# MEZ_Sheet1.net
KiCad netlist of a schematic drawn in Altium Designer
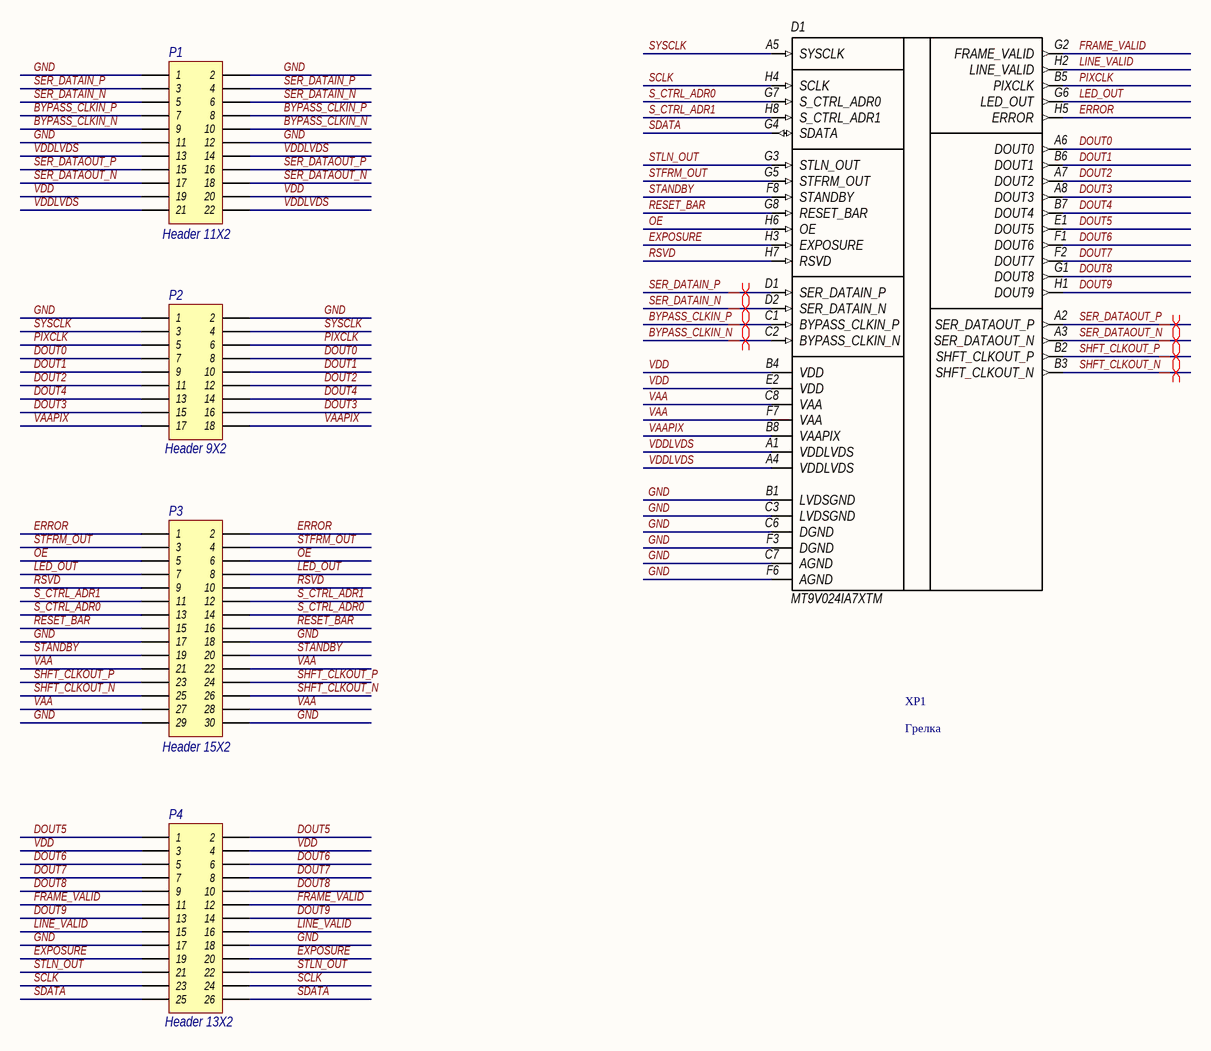
[diagram p0: MEZ_Sheet1.SchDoc]

(export (version "E")
  (design (tool "Eeschema 10.0.6"))
  (components
    (comp (ref "D1")
      (value "MT9V024IA7XTM")
      (footprint "MT9V024IA7XTM")
      (description "КМОП матрица WVGA")
      (libsource (lib "VPL") (part "MT9V024IA7XTM"))
    )
    (comp (ref "P1")
      (value "Header 11X2")
      (footprint "HDR2X11")
      (description "Header, 11-Pin, Dual row")
      (fields (field (name "PUBLISHER") "Altium Limited"))
      (libsource (lib "Miscellaneous Connectors") (part "Header 11X2"))
    )
    (comp (ref "P2")
      (value "Header 9X2")
      (footprint "HDR2X9")
      (description "Header, 9-Pin, Dual row")
      (fields (field (name "PUBLISHER") "Altium Limited"))
      (libsource (lib "Miscellaneous Connectors") (part "Header 9X2"))
    )
    (comp (ref "P3")
      (value "Header 15X2")
      (footprint "HDR2X15")
      (description "Header, 15-Pin, Dual row")
      (fields (field (name "PUBLISHER") "Altium Limited"))
      (libsource (lib "Miscellaneous Connectors") (part "Header 15X2"))
    )
    (comp (ref "P4")
      (value "Header 13X2")
      (footprint "HDR2X13")
      (description "Header, 13-Pin, Dual row")
      (fields (field (name "PUBLISHER") "Altium Limited"))
      (libsource (lib "Miscellaneous Connectors") (part "Header 13X2"))
    )
    (comp (ref "XP1") (value "Грелка") (footprint "Грелка") (libsource (lib "VPL") (part "Грелка")))
  )
  (nets
    (net (code "1") (name "/BYPASS_CLKIN_N") (class "Default")
      (node (ref "D1") (pin "C2") (pinfunction "BYPASS_CLKIN_N_C2") (pintype "input"))
      (node (ref "P1") (pin "10") (pinfunction "10_10") (pintype "passive"))
      (node (ref "P1") (pin "9") (pinfunction "9_9") (pintype "passive"))
    )
    (net (code "2") (name "/BYPASS_CLKIN_P") (class "Default")
      (node (ref "D1") (pin "C1") (pinfunction "BYPASS_CLKIN_P_C1") (pintype "input"))
      (node (ref "P1") (pin "7") (pinfunction "7_7") (pintype "passive"))
      (node (ref "P1") (pin "8") (pinfunction "8_8") (pintype "passive"))
    )
    (net (code "3") (name "/DOUT0") (class "Default")
      (node (ref "D1") (pin "A6") (pinfunction "DOUT0_A6") (pintype "output"))
      (node (ref "P2") (pin "7") (pinfunction "7_7") (pintype "passive"))
      (node (ref "P2") (pin "8") (pinfunction "8_8") (pintype "passive"))
    )
    (net (code "4") (name "/DOUT1") (class "Default")
      (node (ref "D1") (pin "B6") (pinfunction "DOUT1_B6") (pintype "output"))
      (node (ref "P2") (pin "10") (pinfunction "10_10") (pintype "passive"))
      (node (ref "P2") (pin "9") (pinfunction "9_9") (pintype "passive"))
    )
    (net (code "5") (name "/DOUT2") (class "Default")
      (node (ref "D1") (pin "A7") (pinfunction "DOUT2_A7") (pintype "output"))
      (node (ref "P2") (pin "11") (pinfunction "11_11") (pintype "passive"))
      (node (ref "P2") (pin "12") (pinfunction "12_12") (pintype "passive"))
    )
    (net (code "6") (name "/DOUT3") (class "Default")
      (node (ref "D1") (pin "A8") (pinfunction "DOUT3_A8") (pintype "output"))
      (node (ref "P2") (pin "15") (pinfunction "15_15") (pintype "passive"))
      (node (ref "P2") (pin "16") (pinfunction "16_16") (pintype "passive"))
    )
    (net (code "7") (name "/DOUT4") (class "Default")
      (node (ref "D1") (pin "B7") (pinfunction "DOUT4_B7") (pintype "output"))
      (node (ref "P2") (pin "13") (pinfunction "13_13") (pintype "passive"))
      (node (ref "P2") (pin "14") (pinfunction "14_14") (pintype "passive"))
    )
    (net (code "8") (name "/DOUT5") (class "Default")
      (node (ref "D1") (pin "E1") (pinfunction "DOUT5_E1") (pintype "output"))
      (node (ref "P4") (pin "1") (pinfunction "1_1") (pintype "passive"))
      (node (ref "P4") (pin "2") (pinfunction "2_2") (pintype "passive"))
    )
    (net (code "9") (name "/DOUT6") (class "Default")
      (node (ref "D1") (pin "F1") (pinfunction "DOUT6_F1") (pintype "output"))
      (node (ref "P4") (pin "5") (pinfunction "5_5") (pintype "passive"))
      (node (ref "P4") (pin "6") (pinfunction "6_6") (pintype "passive"))
    )
    (net (code "10") (name "/DOUT7") (class "Default")
      (node (ref "D1") (pin "F2") (pinfunction "DOUT7_F2") (pintype "output"))
      (node (ref "P4") (pin "7") (pinfunction "7_7") (pintype "passive"))
      (node (ref "P4") (pin "8") (pinfunction "8_8") (pintype "passive"))
    )
    (net (code "11") (name "/DOUT8") (class "Default")
      (node (ref "D1") (pin "G1") (pinfunction "DOUT8_G1") (pintype "output"))
      (node (ref "P4") (pin "10") (pinfunction "10_10") (pintype "passive"))
      (node (ref "P4") (pin "9") (pinfunction "9_9") (pintype "passive"))
    )
    (net (code "12") (name "/DOUT9") (class "Default")
      (node (ref "D1") (pin "H1") (pinfunction "DOUT9_H1") (pintype "output"))
      (node (ref "P4") (pin "13") (pinfunction "13_13") (pintype "passive"))
      (node (ref "P4") (pin "14") (pinfunction "14_14") (pintype "passive"))
    )
    (net (code "13") (name "/ERROR") (class "Default")
      (node (ref "D1") (pin "H5") (pinfunction "ERROR_H5") (pintype "output"))
      (node (ref "P3") (pin "1") (pinfunction "1_1") (pintype "passive"))
      (node (ref "P3") (pin "2") (pinfunction "2_2") (pintype "passive"))
    )
    (net (code "14") (name "/EXPOSURE") (class "Default")
      (node (ref "D1") (pin "H3") (pinfunction "EXPOSURE_H3") (pintype "input"))
      (node (ref "P4") (pin "19") (pinfunction "19_19") (pintype "passive"))
      (node (ref "P4") (pin "20") (pinfunction "20_20") (pintype "passive"))
    )
    (net (code "15") (name "/FRAME_VALID") (class "Default")
      (node (ref "D1") (pin "G2") (pinfunction "FRAME_VALID_G2") (pintype "output"))
      (node (ref "P4") (pin "11") (pinfunction "11_11") (pintype "passive"))
      (node (ref "P4") (pin "12") (pinfunction "12_12") (pintype "passive"))
    )
    (net (code "16") (name "/GND") (class "Default")
      (node (ref "D1") (pin "B1") (pinfunction "LVDSGND_B1") (pintype "passive"))
      (node (ref "D1") (pin "C3") (pinfunction "LVDSGND_C3") (pintype "passive"))
      (node (ref "D1") (pin "C6") (pinfunction "DGND_C6") (pintype "passive"))
      (node (ref "D1") (pin "C7") (pinfunction "AGND_C7") (pintype "passive"))
      (node (ref "D1") (pin "F3") (pinfunction "DGND_F3") (pintype "passive"))
      (node (ref "D1") (pin "F6") (pinfunction "AGND_F6") (pintype "passive"))
      (node (ref "P1") (pin "1") (pinfunction "1_1") (pintype "passive"))
      (node (ref "P1") (pin "11") (pinfunction "11_11") (pintype "passive"))
      (node (ref "P1") (pin "12") (pinfunction "12_12") (pintype "passive"))
      (node (ref "P1") (pin "2") (pinfunction "2_2") (pintype "passive"))
      (node (ref "P2") (pin "1") (pinfunction "1_1") (pintype "passive"))
      (node (ref "P2") (pin "2") (pinfunction "2_2") (pintype "passive"))
      (node (ref "P3") (pin "17") (pinfunction "17_17") (pintype "passive"))
      (node (ref "P3") (pin "18") (pinfunction "18_18") (pintype "passive"))
      (node (ref "P3") (pin "29") (pinfunction "29_29") (pintype "passive"))
      (node (ref "P3") (pin "30") (pinfunction "30_30") (pintype "passive"))
      (node (ref "P4") (pin "17") (pinfunction "17_17") (pintype "passive"))
      (node (ref "P4") (pin "18") (pinfunction "18_18") (pintype "passive"))
    )
    (net (code "17") (name "/LED_OUT") (class "Default")
      (node (ref "D1") (pin "G6") (pinfunction "LED_OUT_G6") (pintype "output"))
      (node (ref "P3") (pin "7") (pinfunction "7_7") (pintype "passive"))
      (node (ref "P3") (pin "8") (pinfunction "8_8") (pintype "passive"))
    )
    (net (code "18") (name "/LINE_VALID") (class "Default")
      (node (ref "D1") (pin "H2") (pinfunction "LINE_VALID_H2") (pintype "output"))
      (node (ref "P4") (pin "15") (pinfunction "15_15") (pintype "passive"))
      (node (ref "P4") (pin "16") (pinfunction "16_16") (pintype "passive"))
    )
    (net (code "19") (name "/OE") (class "Default")
      (node (ref "D1") (pin "H6") (pinfunction "OE_H6") (pintype "input"))
      (node (ref "P3") (pin "5") (pinfunction "5_5") (pintype "passive"))
      (node (ref "P3") (pin "6") (pinfunction "6_6") (pintype "passive"))
    )
    (net (code "20") (name "/PIXCLK") (class "Default")
      (node (ref "D1") (pin "B5") (pinfunction "PIXCLK_B5") (pintype "output"))
      (node (ref "P2") (pin "5") (pinfunction "5_5") (pintype "passive"))
      (node (ref "P2") (pin "6") (pinfunction "6_6") (pintype "passive"))
    )
    (net (code "21") (name "/RESET_BAR") (class "Default")
      (node (ref "D1") (pin "G8") (pinfunction "RESET_BAR_G8") (pintype "input"))
      (node (ref "P3") (pin "15") (pinfunction "15_15") (pintype "passive"))
      (node (ref "P3") (pin "16") (pinfunction "16_16") (pintype "passive"))
    )
    (net (code "22") (name "/RSVD") (class "Default")
      (node (ref "D1") (pin "H7") (pinfunction "RSVD_H7") (pintype "input"))
      (node (ref "P3") (pin "10") (pinfunction "10_10") (pintype "passive"))
      (node (ref "P3") (pin "9") (pinfunction "9_9") (pintype "passive"))
    )
    (net (code "23") (name "/SCLK") (class "Default")
      (node (ref "D1") (pin "H4") (pinfunction "SCLK_H4") (pintype "input"))
      (node (ref "P4") (pin "23") (pinfunction "23_23") (pintype "passive"))
      (node (ref "P4") (pin "24") (pinfunction "24_24") (pintype "passive"))
    )
    (net (code "24") (name "/SDATA") (class "Default")
      (node (ref "D1") (pin "G4") (pinfunction "SDATA_G4") (pintype "bidirectional"))
      (node (ref "P4") (pin "25") (pinfunction "25_25") (pintype "passive"))
      (node (ref "P4") (pin "26") (pinfunction "26_26") (pintype "passive"))
    )
    (net (code "25") (name "/SER_DATAIN_N") (class "Default")
      (node (ref "D1") (pin "D2") (pinfunction "SER_DATAIN_N_D2") (pintype "input"))
      (node (ref "P1") (pin "5") (pinfunction "5_5") (pintype "passive"))
      (node (ref "P1") (pin "6") (pinfunction "6_6") (pintype "passive"))
    )
    (net (code "26") (name "/SER_DATAIN_P") (class "Default")
      (node (ref "D1") (pin "D1") (pinfunction "SER_DATAIN_P_D1") (pintype "input"))
      (node (ref "P1") (pin "3") (pinfunction "3_3") (pintype "passive"))
      (node (ref "P1") (pin "4") (pinfunction "4_4") (pintype "passive"))
    )
    (net (code "27") (name "/SER_DATAOUT_N") (class "Default")
      (node (ref "D1") (pin "A3") (pinfunction "SER_DATAOUT_N_A3") (pintype "output"))
      (node (ref "P1") (pin "17") (pinfunction "17_17") (pintype "passive"))
      (node (ref "P1") (pin "18") (pinfunction "18_18") (pintype "passive"))
    )
    (net (code "28") (name "/SER_DATAOUT_P") (class "Default")
      (node (ref "D1") (pin "A2") (pinfunction "SER_DATAOUT_P_A2") (pintype "output"))
      (node (ref "P1") (pin "15") (pinfunction "15_15") (pintype "passive"))
      (node (ref "P1") (pin "16") (pinfunction "16_16") (pintype "passive"))
    )
    (net (code "29") (name "/SHFT_CLKOUT_N") (class "Default")
      (node (ref "D1") (pin "B3") (pinfunction "SHFT_CLKOUT_N_B3") (pintype "output"))
      (node (ref "P3") (pin "25") (pinfunction "25_25") (pintype "passive"))
      (node (ref "P3") (pin "26") (pinfunction "26_26") (pintype "passive"))
    )
    (net (code "30") (name "/SHFT_CLKOUT_P") (class "Default")
      (node (ref "D1") (pin "B2") (pinfunction "SHFT_CLKOUT_P_B2") (pintype "output"))
      (node (ref "P3") (pin "23") (pinfunction "23_23") (pintype "passive"))
      (node (ref "P3") (pin "24") (pinfunction "24_24") (pintype "passive"))
    )
    (net (code "31") (name "/STANDBY") (class "Default")
      (node (ref "D1") (pin "F8") (pinfunction "STANDBY_F8") (pintype "input"))
      (node (ref "P3") (pin "19") (pinfunction "19_19") (pintype "passive"))
      (node (ref "P3") (pin "20") (pinfunction "20_20") (pintype "passive"))
    )
    (net (code "32") (name "/STFRM_OUT") (class "Default")
      (node (ref "D1") (pin "G5") (pinfunction "STFRM_OUT_G5") (pintype "input"))
      (node (ref "P3") (pin "3") (pinfunction "3_3") (pintype "passive"))
      (node (ref "P3") (pin "4") (pinfunction "4_4") (pintype "passive"))
    )
    (net (code "33") (name "/STLN_OUT") (class "Default")
      (node (ref "D1") (pin "G3") (pinfunction "STLN_OUT_G3") (pintype "input"))
      (node (ref "P4") (pin "21") (pinfunction "21_21") (pintype "passive"))
      (node (ref "P4") (pin "22") (pinfunction "22_22") (pintype "passive"))
    )
    (net (code "34") (name "/SYSCLK") (class "Default")
      (node (ref "D1") (pin "A5") (pinfunction "SYSCLK_A5") (pintype "input"))
      (node (ref "P2") (pin "3") (pinfunction "3_3") (pintype "passive"))
      (node (ref "P2") (pin "4") (pinfunction "4_4") (pintype "passive"))
    )
    (net (code "35") (name "/S_CTRL_ADR0") (class "Default")
      (node (ref "D1") (pin "G7") (pinfunction "S_CTRL_ADR0_G7") (pintype "input"))
      (node (ref "P3") (pin "13") (pinfunction "13_13") (pintype "passive"))
      (node (ref "P3") (pin "14") (pinfunction "14_14") (pintype "passive"))
    )
    (net (code "36") (name "/S_CTRL_ADR1") (class "Default")
      (node (ref "D1") (pin "H8") (pinfunction "S_CTRL_ADR1_H8") (pintype "input"))
      (node (ref "P3") (pin "11") (pinfunction "11_11") (pintype "passive"))
      (node (ref "P3") (pin "12") (pinfunction "12_12") (pintype "passive"))
    )
    (net (code "37") (name "/VAA") (class "Default")
      (node (ref "D1") (pin "C8") (pinfunction "VAA_C8") (pintype "passive"))
      (node (ref "D1") (pin "F7") (pinfunction "VAA_F7") (pintype "passive"))
      (node (ref "P3") (pin "21") (pinfunction "21_21") (pintype "passive"))
      (node (ref "P3") (pin "22") (pinfunction "22_22") (pintype "passive"))
      (node (ref "P3") (pin "27") (pinfunction "27_27") (pintype "passive"))
      (node (ref "P3") (pin "28") (pinfunction "28_28") (pintype "passive"))
    )
    (net (code "38") (name "/VAAPIX") (class "Default")
      (node (ref "D1") (pin "B8") (pinfunction "VAAPIX_B8") (pintype "passive"))
      (node (ref "P2") (pin "17") (pinfunction "17_17") (pintype "passive"))
      (node (ref "P2") (pin "18") (pinfunction "18_18") (pintype "passive"))
    )
    (net (code "39") (name "/VDD") (class "Default")
      (node (ref "D1") (pin "B4") (pinfunction "VDD_B4") (pintype "passive"))
      (node (ref "D1") (pin "E2") (pinfunction "VDD_E2") (pintype "passive"))
      (node (ref "P1") (pin "19") (pinfunction "19_19") (pintype "passive"))
      (node (ref "P1") (pin "20") (pinfunction "20_20") (pintype "passive"))
      (node (ref "P4") (pin "3") (pinfunction "3_3") (pintype "passive"))
      (node (ref "P4") (pin "4") (pinfunction "4_4") (pintype "passive"))
    )
    (net (code "40") (name "/VDDLVDS") (class "Default")
      (node (ref "D1") (pin "A1") (pinfunction "VDDLVDS_A1") (pintype "passive"))
      (node (ref "D1") (pin "A4") (pinfunction "VDDLVDS_A4") (pintype "passive"))
      (node (ref "P1") (pin "13") (pinfunction "13_13") (pintype "passive"))
      (node (ref "P1") (pin "14") (pinfunction "14_14") (pintype "passive"))
      (node (ref "P1") (pin "21") (pinfunction "21_21") (pintype "passive"))
      (node (ref "P1") (pin "22") (pinfunction "22_22") (pintype "passive"))
    )
  )
)
